# Sheet1.net
KiCad netlist of a schematic drawn in Altium Designer
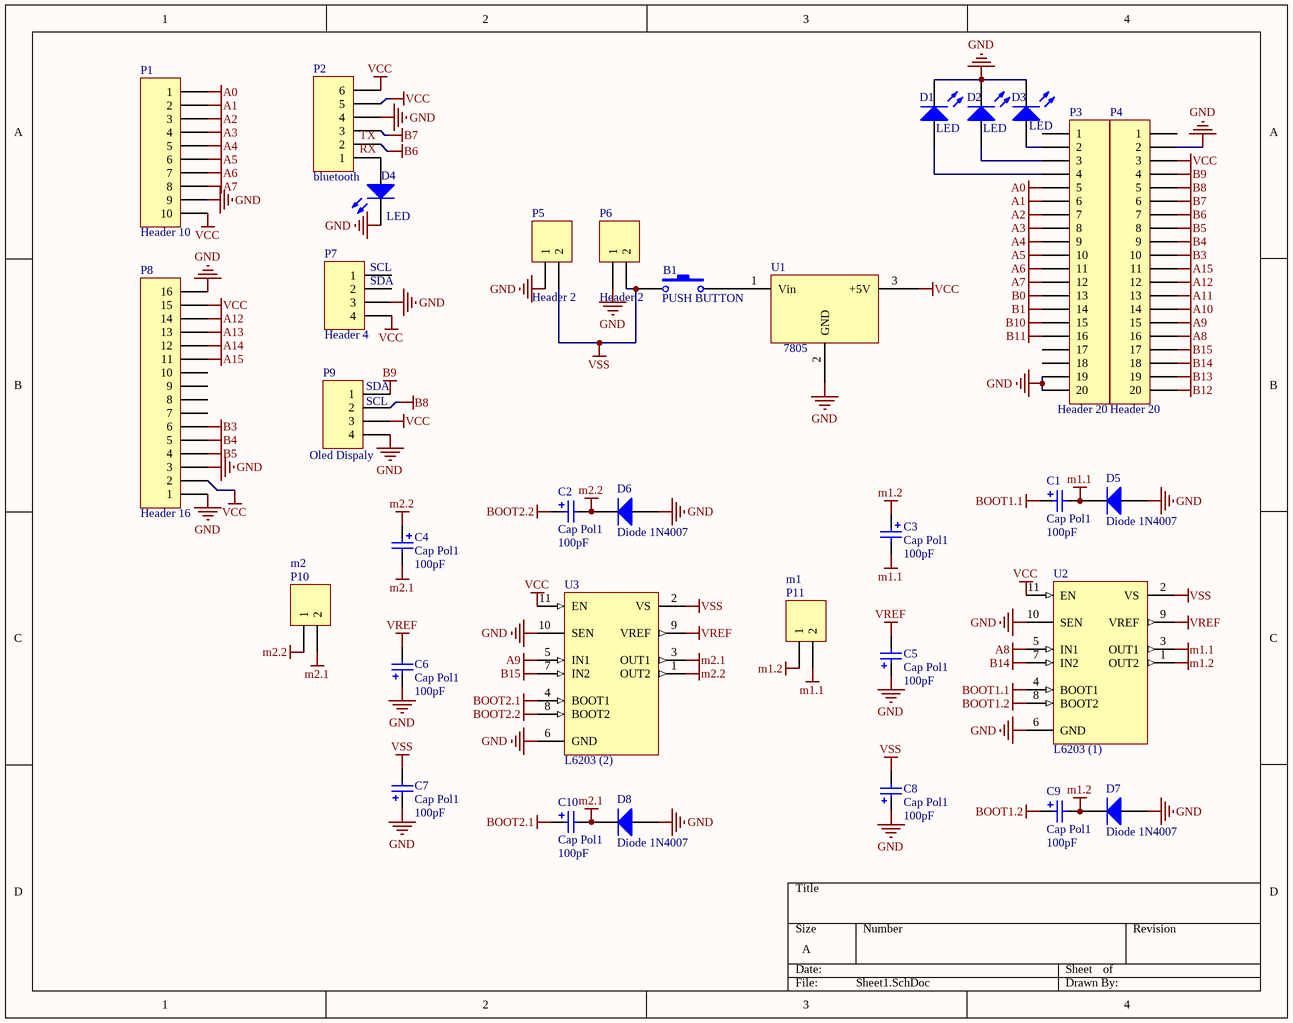
[diagram p0: Sheet1.SchDoc]

(export (version "E")
  (design (tool "Eeschema 10.0.6"))
  (components
    (comp (ref "B1")
      (value "PUSH BUTTON")
      (footprint "MY_SPST_2")
      (libsource (lib "AMINLIB") (part "PUSH BUTTON"))
    )
    (comp (ref "C1")
      (value "Cap Pol1")
      (footprint "HDR1X2")
      (description "Polarized Capacitor (Radial)")
      (fields (field (name "ALTIUM_VALUE") "100pF") (field (name "PUBLISHER") "Altium Limited"))
      (libsource (lib "Soccer1") (part "Cap Pol1"))
    )
    (comp (ref "C2")
      (value "Cap Pol1")
      (footprint "HDR1X2")
      (description "Polarized Capacitor (Radial)")
      (fields (field (name "ALTIUM_VALUE") "100pF") (field (name "PUBLISHER") "Altium Limited"))
      (libsource (lib "Soccer1") (part "Cap Pol1"))
    )
    (comp (ref "C3")
      (value "Cap Pol1")
      (footprint "HDR1X2")
      (description "Polarized Capacitor (Radial)")
      (fields (field (name "ALTIUM_VALUE") "100pF") (field (name "PUBLISHER") "Altium Limited"))
      (libsource (lib "Soccer1") (part "Cap Pol1"))
    )
    (comp (ref "C4")
      (value "Cap Pol1")
      (footprint "HDR1X2")
      (description "Polarized Capacitor (Radial)")
      (fields (field (name "ALTIUM_VALUE") "100pF") (field (name "PUBLISHER") "Altium Limited"))
      (libsource (lib "Soccer1") (part "Cap Pol1"))
    )
    (comp (ref "C5")
      (value "Cap Pol1")
      (footprint "HDR1X2")
      (description "Polarized Capacitor (Radial)")
      (fields (field (name "ALTIUM_VALUE") "100pF") (field (name "PUBLISHER") "Altium Limited"))
      (libsource (lib "Soccer1") (part "Cap Pol1"))
    )
    (comp (ref "C6")
      (value "Cap Pol1")
      (footprint "HDR1X2")
      (description "Polarized Capacitor (Radial)")
      (fields (field (name "ALTIUM_VALUE") "100pF") (field (name "PUBLISHER") "Altium Limited"))
      (libsource (lib "Soccer1") (part "Cap Pol1"))
    )
    (comp (ref "C7")
      (value "Cap Pol1")
      (footprint "HDR1X2")
      (description "Polarized Capacitor (Radial)")
      (fields (field (name "ALTIUM_VALUE") "100pF") (field (name "PUBLISHER") "Altium Limited"))
      (libsource (lib "Soccer1") (part "Cap Pol1"))
    )
    (comp (ref "C8")
      (value "Cap Pol1")
      (footprint "HDR1X2")
      (description "Polarized Capacitor (Radial)")
      (fields (field (name "ALTIUM_VALUE") "100pF") (field (name "PUBLISHER") "Altium Limited"))
      (libsource (lib "Soccer1") (part "Cap Pol1"))
    )
    (comp (ref "C9")
      (value "Cap Pol1")
      (footprint "HDR1X2")
      (description "Polarized Capacitor (Radial)")
      (fields (field (name "ALTIUM_VALUE") "100pF") (field (name "PUBLISHER") "Altium Limited"))
      (libsource (lib "Soccer1") (part "Cap Pol1"))
    )
    (comp (ref "C10")
      (value "Cap Pol1")
      (footprint "HDR1X2")
      (description "Polarized Capacitor (Radial)")
      (fields (field (name "ALTIUM_VALUE") "100pF") (field (name "PUBLISHER") "Altium Limited"))
      (libsource (lib "Soccer1") (part "Cap Pol1"))
    )
    (comp (ref "D1")
      (value "LED")
      (footprint "My_LED3MM")
      (description "Typical INFRARED GaAs LED")
      (fields (field (name "PUBLISHER") "Altium Limited"))
      (libsource (lib "AMINLIB") (part "LED"))
    )
    (comp (ref "D2")
      (value "LED")
      (footprint "My_LED3MM")
      (description "Typical INFRARED GaAs LED")
      (fields (field (name "PUBLISHER") "Altium Limited"))
      (libsource (lib "AMINLIB") (part "LED"))
    )
    (comp (ref "D3")
      (value "LED")
      (footprint "My_LED3MM")
      (description "Typical INFRARED GaAs LED")
      (fields (field (name "PUBLISHER") "Altium Limited"))
      (libsource (lib "AMINLIB") (part "LED"))
    )
    (comp (ref "D4")
      (value "LED")
      (footprint "My_LED3MM")
      (description "Typical INFRARED GaAs LED")
      (fields (field (name "PUBLISHER") "Altium Limited"))
      (libsource (lib "AMINLIB") (part "LED"))
    )
    (comp (ref "D5")
      (value "Diode 1N4007")
      (footprint "DO-41")
      (description "1 Amp General Purpose Rectifier")
      (fields (field (name "PUBLISHER") "Altium Limited"))
      (libsource (lib "Soccer1") (part "Diode 1N4007"))
    )
    (comp (ref "D6")
      (value "Diode 1N4007")
      (footprint "DO-41")
      (description "1 Amp General Purpose Rectifier")
      (fields (field (name "PUBLISHER") "Altium Limited"))
      (libsource (lib "Soccer1") (part "Diode 1N4007"))
    )
    (comp (ref "D7")
      (value "Diode 1N4007")
      (footprint "DO-41")
      (description "1 Amp General Purpose Rectifier")
      (fields (field (name "PUBLISHER") "Altium Limited"))
      (libsource (lib "Soccer1") (part "Diode 1N4007"))
    )
    (comp (ref "D8")
      (value "Diode 1N4007")
      (footprint "DO-41")
      (description "1 Amp General Purpose Rectifier")
      (fields (field (name "PUBLISHER") "Altium Limited"))
      (libsource (lib "Soccer1") (part "Diode 1N4007"))
    )
    (comp (ref "P1")
      (value "Header 10")
      (footprint "HDR1X10")
      (description "Header, 10-Pin")
      (fields (field (name "PUBLISHER") "Altium Limited"))
      (libsource (lib "Miscellaneous Connectors") (part "Header 10"))
    )
    (comp (ref "P2")
      (value "bluetooth")
      (footprint "HDR1X6")
      (description "Header, 6-Pin")
      (fields (field (name "PUBLISHER") "Altium Limited"))
      (libsource (lib "footbalist1") (part "Header 6"))
    )
    (comp (ref "P3")
      (value "Header 20")
      (footprint "HDR1X20")
      (description "Header, 20-Pin")
      (fields (field (name "PUBLISHER") "Altium Limited"))
      (libsource (lib "Miscellaneous Connectors") (part "Header 20"))
    )
    (comp (ref "P4")
      (value "Header 20")
      (footprint "HDR1X20")
      (description "Header, 20-Pin")
      (fields (field (name "PUBLISHER") "Altium Limited"))
      (libsource (lib "") (part "Header 20_1"))
    )
    (comp (ref "P5")
      (value "Header 2")
      (footprint "HDR1X2")
      (description "Header, 2-Pin")
      (fields (field (name "PUBLISHER") "Altium Limited"))
      (libsource (lib "Miscellaneous Connectors") (part "Header 2"))
    )
    (comp (ref "P6")
      (value "Header 2")
      (footprint "HDR1X2")
      (description "Header, 2-Pin")
      (fields (field (name "PUBLISHER") "Altium Limited"))
      (libsource (lib "Miscellaneous Connectors") (part "Header 2"))
    )
    (comp (ref "P7")
      (value "Header 4")
      (footprint "HDR1X4")
      (description "Header, 4-Pin")
      (fields (field (name "PUBLISHER") "Altium Limited"))
      (libsource (lib "Miscellaneous Connectors") (part "Header 4"))
    )
    (comp (ref "P8")
      (value "Header 16")
      (footprint "HDR1X16")
      (description "Header, 16-Pin")
      (fields (field (name "PUBLISHER") "Altium Limited"))
      (libsource (lib "Miscellaneous Connectors") (part "Header 16"))
    )
    (comp (ref "P9")
      (value "Oled Dispaly")
      (footprint "HDR1X4")
      (description "Header, 4-Pin")
      (fields (field (name "PUBLISHER") "Altium Limited"))
      (libsource (lib "Miscellaneous Connectors") (part "Header 4"))
    )
    (comp (ref "P10")
      (value "m2")
      (footprint "HDR1X2")
      (description "Header, 2-Pin")
      (fields (field (name "PUBLISHER") "Altium Limited"))
      (libsource (lib "Soccer1") (part "Header 2"))
    )
    (comp (ref "P11")
      (value "m1")
      (footprint "HDR1X2")
      (description "Header, 2-Pin")
      (fields (field (name "PUBLISHER") "Altium Limited"))
      (libsource (lib "Soccer1") (part "Header 2"))
    )
    (comp (ref "U1")
      (value "7805")
      (footprint "My_TO-220")
      (description "Regulator")
      (libsource (lib "AMINLIB") (part "7805"))
    )
    (comp (ref "U2")
      (value "L6203 (1)")
      (footprint "Multiwatt11")
      (description "DMOS Full Bridge Driver")
      (fields (field (name "PUBLISHER") "Altium Limited"))
      (libsource (lib "Soccer1") (part "L6203"))
    )
    (comp (ref "U3")
      (value "L6203 (2)")
      (footprint "Multiwatt11")
      (description "DMOS Full Bridge Driver")
      (fields (field (name "PUBLISHER") "Altium Limited"))
      (libsource (lib "Soccer1") (part "L6203"))
    )
  )
  (nets
    (net (code "1") (name "A0") (class "Default")
      (node (ref "P1") (pin "1") (pinfunction "1_1") (pintype "passive"))
      (node (ref "P3") (pin "5") (pinfunction "5_5") (pintype "passive"))
    )
    (net (code "2") (name "A1") (class "Default")
      (node (ref "P1") (pin "2") (pinfunction "2_2") (pintype "passive"))
      (node (ref "P3") (pin "6") (pinfunction "6_6") (pintype "passive"))
    )
    (net (code "3") (name "A2") (class "Default")
      (node (ref "P1") (pin "3") (pinfunction "3_3") (pintype "passive"))
      (node (ref "P3") (pin "7") (pinfunction "7_7") (pintype "passive"))
    )
    (net (code "4") (name "A3") (class "Default")
      (node (ref "P1") (pin "4") (pinfunction "4_4") (pintype "passive"))
      (node (ref "P3") (pin "8") (pinfunction "8_8") (pintype "passive"))
    )
    (net (code "5") (name "A4") (class "Default")
      (node (ref "P1") (pin "5") (pinfunction "5_5") (pintype "passive"))
      (node (ref "P3") (pin "9") (pinfunction "9_9") (pintype "passive"))
    )
    (net (code "6") (name "A5") (class "Default")
      (node (ref "P1") (pin "6") (pinfunction "6_6") (pintype "passive"))
      (node (ref "P3") (pin "10") (pinfunction "10_10") (pintype "passive"))
    )
    (net (code "7") (name "A6") (class "Default")
      (node (ref "P1") (pin "7") (pinfunction "7_7") (pintype "passive"))
      (node (ref "P3") (pin "11") (pinfunction "11_11") (pintype "passive"))
    )
    (net (code "8") (name "A7") (class "Default")
      (node (ref "P1") (pin "8") (pinfunction "8_8") (pintype "passive"))
      (node (ref "P3") (pin "12") (pinfunction "12_12") (pintype "passive"))
    )
    (net (code "9") (name "A8") (class "Default")
      (node (ref "P4") (pin "16") (pinfunction "16_16") (pintype "passive"))
      (node (ref "U2") (pin "5") (pinfunction "IN1_5") (pintype "input"))
    )
    (net (code "10") (name "A9") (class "Default")
      (node (ref "P4") (pin "15") (pinfunction "15_15") (pintype "passive"))
      (node (ref "U3") (pin "5") (pinfunction "IN1_5") (pintype "input"))
    )
    (net (code "11") (name "A10") (class "Default")
      (node (ref "P4") (pin "14") (pinfunction "14_14") (pintype "passive"))
    )
    (net (code "12") (name "A11") (class "Default")
      (node (ref "P4") (pin "13") (pinfunction "13_13") (pintype "passive"))
    )
    (net (code "13") (name "A12") (class "Default")
      (node (ref "P4") (pin "12") (pinfunction "12_12") (pintype "passive"))
      (node (ref "P8") (pin "14") (pinfunction "14_14") (pintype "passive"))
    )
    (net (code "14") (name "A13") (class "Default")
      (node (ref "P8") (pin "13") (pinfunction "13_13") (pintype "passive"))
    )
    (net (code "15") (name "A14") (class "Default")
      (node (ref "P8") (pin "12") (pinfunction "12_12") (pintype "passive"))
    )
    (net (code "16") (name "A15") (class "Default")
      (node (ref "P4") (pin "11") (pinfunction "11_11") (pintype "passive"))
      (node (ref "P8") (pin "11") (pinfunction "11_11") (pintype "passive"))
    )
    (net (code "17") (name "B0") (class "Default")
      (node (ref "P3") (pin "13") (pinfunction "13_13") (pintype "passive"))
    )
    (net (code "18") (name "B1") (class "Default")
      (node (ref "P3") (pin "14") (pinfunction "14_14") (pintype "passive"))
    )
    (net (code "19") (name "B3") (class "Default")
      (node (ref "P4") (pin "10") (pinfunction "10_10") (pintype "passive"))
      (node (ref "P8") (pin "6") (pinfunction "6_6") (pintype "passive"))
    )
    (net (code "20") (name "B4") (class "Default")
      (node (ref "P4") (pin "9") (pinfunction "9_9") (pintype "passive"))
      (node (ref "P8") (pin "5") (pinfunction "5_5") (pintype "passive"))
    )
    (net (code "21") (name "B5") (class "Default")
      (node (ref "P4") (pin "8") (pinfunction "8_8") (pintype "passive"))
      (node (ref "P8") (pin "4") (pinfunction "4_4") (pintype "passive"))
    )
    (net (code "22") (name "B6") (class "Default")
      (node (ref "P2") (pin "2") (pinfunction "2_2") (pintype "passive"))
      (node (ref "P4") (pin "7") (pinfunction "7_7") (pintype "passive"))
    )
    (net (code "23") (name "B7") (class "Default")
      (node (ref "P2") (pin "3") (pinfunction "3_3") (pintype "passive"))
      (node (ref "P4") (pin "6") (pinfunction "6_6") (pintype "passive"))
    )
    (net (code "24") (name "B8") (class "Default")
      (node (ref "P4") (pin "5") (pinfunction "5_5") (pintype "passive"))
      (node (ref "P9") (pin "2") (pinfunction "2_2") (pintype "passive"))
    )
    (net (code "25") (name "B9") (class "Default")
      (node (ref "P4") (pin "4") (pinfunction "4_4") (pintype "passive"))
      (node (ref "P9") (pin "1") (pinfunction "1_1") (pintype "passive"))
    )
    (net (code "26") (name "B10") (class "Default")
      (node (ref "P3") (pin "15") (pinfunction "15_15") (pintype "passive"))
    )
    (net (code "27") (name "B11") (class "Default")
      (node (ref "P3") (pin "16") (pinfunction "16_16") (pintype "passive"))
    )
    (net (code "28") (name "B12") (class "Default")
      (node (ref "P4") (pin "20") (pinfunction "20_20") (pintype "passive"))
    )
    (net (code "29") (name "B13") (class "Default")
      (node (ref "P4") (pin "19") (pinfunction "19_19") (pintype "passive"))
    )
    (net (code "30") (name "B14") (class "Default")
      (node (ref "P4") (pin "18") (pinfunction "18_18") (pintype "passive"))
      (node (ref "U2") (pin "7") (pinfunction "IN2_7") (pintype "input"))
    )
    (net (code "31") (name "B15") (class "Default")
      (node (ref "P4") (pin "17") (pinfunction "17_17") (pintype "passive"))
      (node (ref "U3") (pin "7") (pinfunction "IN2_7") (pintype "input"))
    )
    (net (code "32") (name "BOOT1.1") (class "Default")
      (node (ref "C1") (pin "1") (pinfunction "1_1") (pintype "passive"))
      (node (ref "U2") (pin "4") (pinfunction "BOOT1_4") (pintype "input"))
    )
    (net (code "33") (name "BOOT1.2") (class "Default")
      (node (ref "C9") (pin "1") (pinfunction "1_1") (pintype "passive"))
      (node (ref "U2") (pin "8") (pinfunction "BOOT2_8") (pintype "input"))
    )
    (net (code "34") (name "BOOT2.1") (class "Default")
      (node (ref "C10") (pin "1") (pinfunction "1_1") (pintype "passive"))
      (node (ref "U3") (pin "4") (pinfunction "BOOT1_4") (pintype "input"))
    )
    (net (code "35") (name "BOOT2.2") (class "Default")
      (node (ref "C2") (pin "1") (pinfunction "1_1") (pintype "passive"))
      (node (ref "U3") (pin "8") (pinfunction "BOOT2_8") (pintype "input"))
    )
    (net (code "36") (name "GND") (class "Default")
      (node (ref "C5") (pin "1") (pinfunction "1_1") (pintype "passive"))
      (node (ref "C6") (pin "1") (pinfunction "1_1") (pintype "passive"))
      (node (ref "C7") (pin "1") (pinfunction "1_1") (pintype "passive"))
      (node (ref "C8") (pin "1") (pinfunction "1_1") (pintype "passive"))
      (node (ref "D1") (pin "K") (pinfunction "K_K") (pintype "passive"))
      (node (ref "D2") (pin "K") (pinfunction "K_K") (pintype "passive"))
      (node (ref "D3") (pin "K") (pinfunction "K_K") (pintype "passive"))
      (node (ref "D4") (pin "K") (pinfunction "K_K") (pintype "passive"))
      (node (ref "D5") (pin "1") (pinfunction "A_1") (pintype "passive"))
      (node (ref "D6") (pin "1") (pinfunction "A_1") (pintype "passive"))
      (node (ref "D7") (pin "1") (pinfunction "A_1") (pintype "passive"))
      (node (ref "D8") (pin "1") (pinfunction "A_1") (pintype "passive"))
      (node (ref "P1") (pin "9") (pinfunction "9_9") (pintype "passive"))
      (node (ref "P2") (pin "4") (pinfunction "4_4") (pintype "passive"))
      (node (ref "P3") (pin "19") (pinfunction "19_19") (pintype "passive"))
      (node (ref "P3") (pin "20") (pinfunction "20_20") (pintype "passive"))
      (node (ref "P4") (pin "2") (pinfunction "2_2") (pintype "passive"))
      (node (ref "P5") (pin "1") (pinfunction "1_1") (pintype "passive"))
      (node (ref "P6") (pin "1") (pinfunction "1_1") (pintype "passive"))
      (node (ref "P8") (pin "1") (pinfunction "1_1") (pintype "passive"))
      (node (ref "P8") (pin "16") (pinfunction "16_16") (pintype "passive"))
      (node (ref "P8") (pin "3") (pinfunction "3_3") (pintype "passive"))
      (node (ref "P9") (pin "4") (pinfunction "4_4") (pintype "passive"))
      (node (ref "U1") (pin "2") (pinfunction "GND_2") (pintype "power_in"))
      (node (ref "U2") (pin "10") (pinfunction "SEN_10") (pintype "passive"))
      (node (ref "U2") (pin "6") (pinfunction "GND_6") (pintype "power_in"))
      (node (ref "U3") (pin "10") (pinfunction "SEN_10") (pintype "passive"))
      (node (ref "U3") (pin "6") (pinfunction "GND_6") (pintype "power_in"))
    )
    (net (code "37") (name "Net-(D1-PadA)") (class "Default")
      (node (ref "D1") (pin "A") (pinfunction "A_A") (pintype "passive"))
      (node (ref "P3") (pin "4") (pinfunction "4_4") (pintype "passive"))
    )
    (net (code "38") (name "Net-(D2-PadA)") (class "Default")
      (node (ref "D2") (pin "A") (pinfunction "A_A") (pintype "passive"))
      (node (ref "P3") (pin "3") (pinfunction "3_3") (pintype "passive"))
    )
    (net (code "39") (name "Net-(D3-PadA)") (class "Default")
      (node (ref "D3") (pin "A") (pinfunction "A_A") (pintype "passive"))
      (node (ref "P3") (pin "2") (pinfunction "2_2") (pintype "passive"))
    )
    (net (code "40") (name "Net-(D4-PadA)") (class "Default")
      (node (ref "D4") (pin "A") (pinfunction "A_A") (pintype "passive"))
      (node (ref "P2") (pin "1") (pinfunction "1_1") (pintype "passive"))
    )
    (net (code "41") (name "Net-(U1-Vin)") (class "Default")
      (node (ref "B1") (pin "2") (pinfunction "2_2") (pintype "passive"))
      (node (ref "U1") (pin "1") (pinfunction "Vin_1") (pintype "power_in"))
    )
    (net (code "42") (name "VCC") (class "Default")
      (node (ref "P1") (pin "10") (pinfunction "10_10") (pintype "passive"))
      (node (ref "P2") (pin "5") (pinfunction "5_5") (pintype "passive"))
      (node (ref "P2") (pin "6") (pinfunction "6_6") (pintype "passive"))
      (node (ref "P4") (pin "3") (pinfunction "3_3") (pintype "passive"))
      (node (ref "P7") (pin "4") (pinfunction "4_4") (pintype "passive"))
      (node (ref "P8") (pin "15") (pinfunction "15_15") (pintype "passive"))
      (node (ref "P8") (pin "2") (pinfunction "2_2") (pintype "passive"))
      (node (ref "P9") (pin "3") (pinfunction "3_3") (pintype "passive"))
      (node (ref "U1") (pin "3") (pinfunction "+5V_3") (pintype "power_in"))
      (node (ref "U2") (pin "11") (pinfunction "EN_11") (pintype "input"))
      (node (ref "U3") (pin "11") (pinfunction "EN_11") (pintype "input"))
    )
    (net (code "43") (name "VREF") (class "Default")
      (node (ref "C5") (pin "2") (pinfunction "2_2") (pintype "passive"))
      (node (ref "C6") (pin "2") (pinfunction "2_2") (pintype "passive"))
      (node (ref "U2") (pin "9") (pinfunction "VREF_9") (pintype "output"))
      (node (ref "U3") (pin "9") (pinfunction "VREF_9") (pintype "output"))
    )
    (net (code "44") (name "VSS") (class "Default")
      (node (ref "B1") (pin "1") (pinfunction "1_1") (pintype "passive"))
      (node (ref "C7") (pin "2") (pinfunction "2_2") (pintype "passive"))
      (node (ref "C8") (pin "2") (pinfunction "2_2") (pintype "passive"))
      (node (ref "P5") (pin "2") (pinfunction "2_2") (pintype "passive"))
      (node (ref "P6") (pin "2") (pinfunction "2_2") (pintype "passive"))
      (node (ref "U2") (pin "2") (pinfunction "VS_2") (pintype "power_in"))
      (node (ref "U3") (pin "2") (pinfunction "VS_2") (pintype "power_in"))
    )
    (net (code "45") (name "m1.1") (class "Default")
      (node (ref "C1") (pin "2") (pinfunction "2_2") (pintype "passive"))
      (node (ref "C3") (pin "2") (pinfunction "2_2") (pintype "passive"))
      (node (ref "D5") (pin "2") (pinfunction "K_2") (pintype "passive"))
      (node (ref "P11") (pin "2") (pinfunction "2_2") (pintype "passive"))
      (node (ref "U2") (pin "3") (pinfunction "OUT1_3") (pintype "output"))
    )
    (net (code "46") (name "m1.2") (class "Default")
      (node (ref "C3") (pin "1") (pinfunction "1_1") (pintype "passive"))
      (node (ref "C9") (pin "2") (pinfunction "2_2") (pintype "passive"))
      (node (ref "D7") (pin "2") (pinfunction "K_2") (pintype "passive"))
      (node (ref "P11") (pin "1") (pinfunction "1_1") (pintype "passive"))
      (node (ref "U2") (pin "1") (pinfunction "OUT2_1") (pintype "output"))
    )
    (net (code "47") (name "m2.1") (class "Default")
      (node (ref "C10") (pin "2") (pinfunction "2_2") (pintype "passive"))
      (node (ref "C4") (pin "2") (pinfunction "2_2") (pintype "passive"))
      (node (ref "D8") (pin "2") (pinfunction "K_2") (pintype "passive"))
      (node (ref "P10") (pin "2") (pinfunction "2_2") (pintype "passive"))
      (node (ref "U3") (pin "3") (pinfunction "OUT1_3") (pintype "output"))
    )
    (net (code "48") (name "m2.2") (class "Default")
      (node (ref "C2") (pin "2") (pinfunction "2_2") (pintype "passive"))
      (node (ref "C4") (pin "1") (pinfunction "1_1") (pintype "passive"))
      (node (ref "D6") (pin "2") (pinfunction "K_2") (pintype "passive"))
      (node (ref "P10") (pin "1") (pinfunction "1_1") (pintype "passive"))
      (node (ref "U3") (pin "1") (pinfunction "OUT2_1") (pintype "output"))
    )
    (net (code "49") (name "unconnected-(P3-Pad1)") (class "Default")
      (node (ref "P3") (pin "1") (pinfunction "1_1") (pintype "passive"))
    )
    (net (code "50") (name "unconnected-(P3-Pad17)") (class "Default")
      (node (ref "P3") (pin "17") (pinfunction "17_17") (pintype "passive"))
    )
    (net (code "51") (name "unconnected-(P3-Pad18)") (class "Default")
      (node (ref "P3") (pin "18") (pinfunction "18_18") (pintype "passive"))
    )
    (net (code "52") (name "unconnected-(P4-Pad1)") (class "Default")
      (node (ref "P4") (pin "1") (pinfunction "1_1") (pintype "passive"))
    )
    (net (code "53") (name "unconnected-(P7-Pad1)") (class "Default")
      (node (ref "P7") (pin "1") (pinfunction "1_1") (pintype "passive"))
    )
    (net (code "54") (name "unconnected-(P7-Pad2)") (class "Default")
      (node (ref "P7") (pin "2") (pinfunction "2_2") (pintype "passive"))
    )
    (net (code "55") (name "unconnected-(P7-Pad3)") (class "Default")
      (node (ref "P7") (pin "3") (pinfunction "3_3") (pintype "passive"))
    )
    (net (code "56") (name "unconnected-(P8-Pad7)") (class "Default")
      (node (ref "P8") (pin "7") (pinfunction "7_7") (pintype "passive"))
    )
    (net (code "57") (name "unconnected-(P8-Pad8)") (class "Default")
      (node (ref "P8") (pin "8") (pinfunction "8_8") (pintype "passive"))
    )
    (net (code "58") (name "unconnected-(P8-Pad9)") (class "Default")
      (node (ref "P8") (pin "9") (pinfunction "9_9") (pintype "passive"))
    )
    (net (code "59") (name "unconnected-(P8-Pad10)") (class "Default")
      (node (ref "P8") (pin "10") (pinfunction "10_10") (pintype "passive"))
    )
  )
)
